# SMeter_RevA.net
KiCad netlist of a schematic drawn in EAGLE
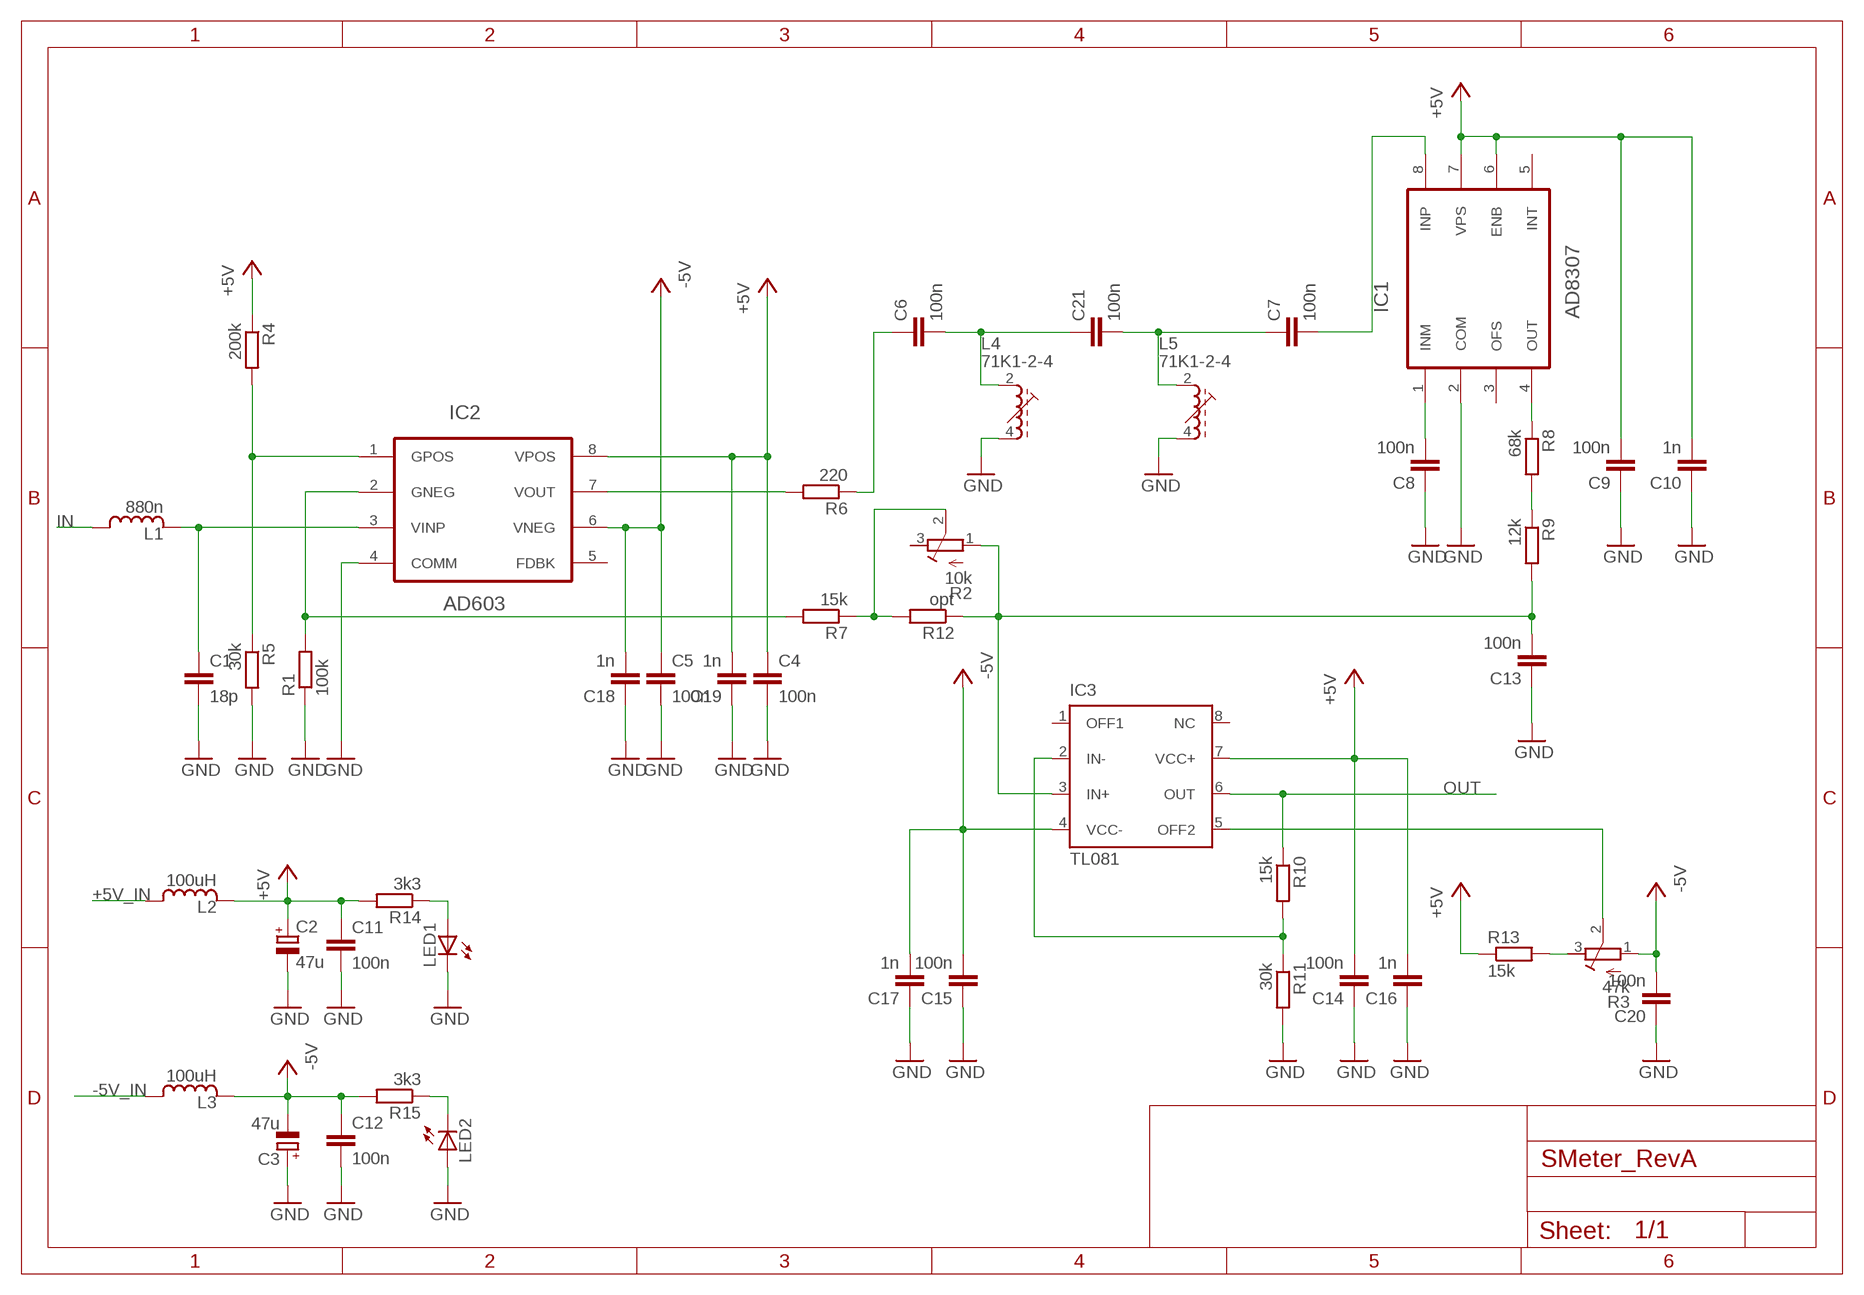
[diagram p0: schematic, sheet 1]

(export (version "E")
  (design (tool "Eeschema 10.0.6"))
  (components
    (comp (ref "C1")
      (value "18p")
      (footprint "eagle-import:C0805")
      (libsource (lib "eagle-import") (part "CC0805"))
    )
    (comp (ref "C2")
      (value "47u")
      (footprint "eagle-import:SMC_B")
      (libsource (lib "eagle-import") (part "C_POLARIZEDSMC_B"))
    )
    (comp (ref "C3")
      (value "47u")
      (footprint "eagle-import:SMC_B")
      (libsource (lib "eagle-import") (part "C_POLARIZEDSMC_B"))
    )
    (comp (ref "C4")
      (value "100n")
      (footprint "eagle-import:C0805")
      (libsource (lib "eagle-import") (part "CC0805"))
    )
    (comp (ref "C5")
      (value "100n")
      (footprint "eagle-import:C0805")
      (libsource (lib "eagle-import") (part "CC0805"))
    )
    (comp (ref "C6")
      (value "100n")
      (footprint "eagle-import:C0805")
      (libsource (lib "eagle-import") (part "CC0805"))
    )
    (comp (ref "C7")
      (value "100n")
      (footprint "eagle-import:C0805")
      (libsource (lib "eagle-import") (part "CC0805"))
    )
    (comp (ref "C8")
      (value "100n")
      (footprint "eagle-import:C0805")
      (libsource (lib "eagle-import") (part "CC0805"))
    )
    (comp (ref "C9")
      (value "100n")
      (footprint "eagle-import:C0805")
      (libsource (lib "eagle-import") (part "CC0805"))
    )
    (comp (ref "C10")
      (value "1n")
      (footprint "eagle-import:C0805")
      (libsource (lib "eagle-import") (part "CC0805"))
    )
    (comp (ref "C11")
      (value "100n")
      (footprint "eagle-import:C0805")
      (libsource (lib "eagle-import") (part "CC0805"))
    )
    (comp (ref "C12")
      (value "100n")
      (footprint "eagle-import:C0805")
      (libsource (lib "eagle-import") (part "CC0805"))
    )
    (comp (ref "C13")
      (value "100n")
      (footprint "eagle-import:C0805")
      (libsource (lib "eagle-import") (part "CC0805"))
    )
    (comp (ref "C14")
      (value "100n")
      (footprint "eagle-import:C0805")
      (libsource (lib "eagle-import") (part "CC0805"))
    )
    (comp (ref "C15")
      (value "100n")
      (footprint "eagle-import:C0805")
      (libsource (lib "eagle-import") (part "CC0805"))
    )
    (comp (ref "C16")
      (value "1n")
      (footprint "eagle-import:C0805")
      (libsource (lib "eagle-import") (part "CC0805"))
    )
    (comp (ref "C17")
      (value "1n")
      (footprint "eagle-import:C0805")
      (libsource (lib "eagle-import") (part "CC0805"))
    )
    (comp (ref "C18")
      (value "1n")
      (footprint "eagle-import:C0805")
      (libsource (lib "eagle-import") (part "CC0805"))
    )
    (comp (ref "C19")
      (value "1n")
      (footprint "eagle-import:C0805")
      (libsource (lib "eagle-import") (part "CC0805"))
    )
    (comp (ref "C20")
      (value "100n")
      (footprint "eagle-import:C0805")
      (libsource (lib "eagle-import") (part "CC0805"))
    )
    (comp (ref "C21")
      (value "100n")
      (footprint "eagle-import:C0805")
      (libsource (lib "eagle-import") (part "CC0805"))
    )
    (comp (ref "IC1")
      (value "AD8307")
      (footprint "eagle-import:SO8")
      (libsource (lib "eagle-import") (part "AD8307"))
    )
    (comp (ref "IC2")
      (value "AD603")
      (footprint "eagle-import:SO8")
      (libsource (lib "eagle-import") (part "AD603"))
    )
    (comp (ref "IC3")
      (value "TL081")
      (footprint "eagle-import:SOIC8")
      (libsource (lib "eagle-import") (part "TL081"))
    )
    (comp (ref "L1")
      (value "880n")
      (footprint "eagle-import:L0805")
      (libsource (lib "eagle-import") (part "INDUCTOR0805"))
    )
    (comp (ref "L2")
      (value "100uH")
      (footprint "eagle-import:LPS4018")
      (libsource (lib "eagle-import") (part "INDUCTORLPS4018"))
    )
    (comp (ref "L3")
      (value "100uH")
      (footprint "eagle-import:LPS4018")
      (libsource (lib "eagle-import") (part "INDUCTORLPS4018"))
    )
    (comp (ref "L4")
      (value "71K1-2-4")
      (footprint "eagle-import:71K")
      (libsource (lib "eagle-import") (part "71K1-2-4"))
    )
    (comp (ref "L5")
      (value "71K1-2-4")
      (footprint "eagle-import:71K")
      (libsource (lib "eagle-import") (part "71K1-2-4"))
    )
    (comp (ref "LED1")
      (value "LED0805")
      (footprint "eagle-import:LED0805")
      (libsource (lib "eagle-import") (part "LED0805"))
    )
    (comp (ref "LED2")
      (value "LED0805")
      (footprint "eagle-import:LED0805")
      (libsource (lib "eagle-import") (part "LED0805"))
    )
    (comp (ref "R1")
      (value "100k")
      (footprint "eagle-import:R0805")
      (libsource (lib "eagle-import") (part "RESISTORR0805"))
    )
    (comp (ref "R2")
      (value "10k")
      (footprint "eagle-import:RTRIM3224X")
      (libsource (lib "eagle-import") (part "TRIMMER3224X"))
    )
    (comp (ref "R3")
      (value "47k")
      (footprint "eagle-import:RTRIM3224X")
      (libsource (lib "eagle-import") (part "TRIMMER3224X"))
    )
    (comp (ref "R4")
      (value "200k")
      (footprint "eagle-import:R0805")
      (libsource (lib "eagle-import") (part "RESISTORR0805"))
    )
    (comp (ref "R5")
      (value "30k")
      (footprint "eagle-import:R0805")
      (libsource (lib "eagle-import") (part "RESISTORR0805"))
    )
    (comp (ref "R6")
      (value "220")
      (footprint "eagle-import:R0805")
      (libsource (lib "eagle-import") (part "RESISTORR0805"))
    )
    (comp (ref "R7")
      (value "15k")
      (footprint "eagle-import:R0805")
      (libsource (lib "eagle-import") (part "RESISTORR0805"))
    )
    (comp (ref "R8")
      (value "68k")
      (footprint "eagle-import:R0805")
      (libsource (lib "eagle-import") (part "RESISTORR0805"))
    )
    (comp (ref "R9")
      (value "12k")
      (footprint "eagle-import:R0805")
      (libsource (lib "eagle-import") (part "RESISTORR0805"))
    )
    (comp (ref "R10")
      (value "15k")
      (footprint "eagle-import:R0805")
      (libsource (lib "eagle-import") (part "RESISTORR0805"))
    )
    (comp (ref "R11")
      (value "30k")
      (footprint "eagle-import:R0805")
      (libsource (lib "eagle-import") (part "RESISTORR0805"))
    )
    (comp (ref "R12")
      (value "opt")
      (footprint "eagle-import:R0805")
      (libsource (lib "eagle-import") (part "RESISTORR0805"))
    )
    (comp (ref "R13")
      (value "15k")
      (footprint "eagle-import:R0805")
      (libsource (lib "eagle-import") (part "RESISTORR0805"))
    )
    (comp (ref "R14")
      (value "3k3")
      (footprint "eagle-import:R0805")
      (libsource (lib "eagle-import") (part "RESISTORR0805"))
    )
    (comp (ref "R15")
      (value "3k3")
      (footprint "eagle-import:R0805")
      (libsource (lib "eagle-import") (part "RESISTORR0805"))
    )
  )
  (nets
    (net (code "1") (name "+5V") (class "Default")
      (node (ref "C10") (pin "2") (pinfunction "2_2") (pintype "passive"))
      (node (ref "C11") (pin "1") (pinfunction "1_1") (pintype "passive"))
      (node (ref "C14") (pin "2") (pinfunction "2_2") (pintype "passive"))
      (node (ref "C16") (pin "2") (pinfunction "2_2") (pintype "passive"))
      (node (ref "C19") (pin "2") (pinfunction "2_2") (pintype "passive"))
      (node (ref "C2") (pin "+") (pinfunction "+_+") (pintype "passive"))
      (node (ref "C4") (pin "1") (pinfunction "1_1") (pintype "passive"))
      (node (ref "C9") (pin "2") (pinfunction "2_2") (pintype "passive"))
      (node (ref "IC1") (pin "6") (pinfunction "ENB_6") (pintype "passive"))
      (node (ref "IC1") (pin "7") (pinfunction "VPS_7") (pintype "passive"))
      (node (ref "IC2") (pin "8") (pinfunction "VPOS_8") (pintype "power_in"))
      (node (ref "IC3") (pin "7") (pinfunction "VCC+_7") (pintype "input"))
      (node (ref "L2") (pin "2") (pinfunction "2_2") (pintype "passive"))
      (node (ref "R13") (pin "1") (pinfunction "1_1") (pintype "passive"))
      (node (ref "R14") (pin "2") (pinfunction "2_2") (pintype "passive"))
      (node (ref "R4") (pin "1") (pinfunction "1_1") (pintype "passive"))
    )
    (net (code "2") (name "-5V") (class "Default")
      (node (ref "C12") (pin "1") (pinfunction "1_1") (pintype "passive"))
      (node (ref "C15") (pin "2") (pinfunction "2_2") (pintype "passive"))
      (node (ref "C17") (pin "2") (pinfunction "2_2") (pintype "passive"))
      (node (ref "C18") (pin "2") (pinfunction "2_2") (pintype "passive"))
      (node (ref "C20") (pin "2") (pinfunction "2_2") (pintype "passive"))
      (node (ref "C3") (pin "-") (pinfunction "-_-") (pintype "passive"))
      (node (ref "C5") (pin "1") (pinfunction "1_1") (pintype "passive"))
      (node (ref "IC2") (pin "6") (pinfunction "VNEG_6") (pintype "passive"))
      (node (ref "IC3") (pin "4") (pinfunction "VCC-_4") (pintype "power_in"))
      (node (ref "L3") (pin "2") (pinfunction "2_2") (pintype "passive"))
      (node (ref "R15") (pin "2") (pinfunction "2_2") (pintype "passive"))
      (node (ref "R3") (pin "1") (pinfunction "CCW_1") (pintype "passive"))
    )
    (net (code "3") (name "/+5V_IN") (class "Default")
      (node (ref "L2") (pin "1") (pinfunction "1_1") (pintype "passive"))
    )
    (net (code "4") (name "/-5V_IN") (class "Default")
      (node (ref "L3") (pin "1") (pinfunction "1_1") (pintype "passive"))
    )
    (net (code "5") (name "/IN") (class "Default")
      (node (ref "L1") (pin "1") (pinfunction "1_1") (pintype "passive"))
    )
    (net (code "6") (name "/OUT") (class "Default")
      (node (ref "IC3") (pin "6") (pinfunction "OUT_6") (pintype "passive"))
      (node (ref "R10") (pin "1") (pinfunction "1_1") (pintype "passive"))
    )
    (net (code "7") (name "GND") (class "Default")
      (node (ref "C1") (pin "2") (pinfunction "2_2") (pintype "passive"))
      (node (ref "C10") (pin "1") (pinfunction "1_1") (pintype "passive"))
      (node (ref "C11") (pin "2") (pinfunction "2_2") (pintype "passive"))
      (node (ref "C12") (pin "2") (pinfunction "2_2") (pintype "passive"))
      (node (ref "C13") (pin "1") (pinfunction "1_1") (pintype "passive"))
      (node (ref "C14") (pin "1") (pinfunction "1_1") (pintype "passive"))
      (node (ref "C15") (pin "1") (pinfunction "1_1") (pintype "passive"))
      (node (ref "C16") (pin "1") (pinfunction "1_1") (pintype "passive"))
      (node (ref "C17") (pin "1") (pinfunction "1_1") (pintype "passive"))
      (node (ref "C18") (pin "1") (pinfunction "1_1") (pintype "passive"))
      (node (ref "C19") (pin "1") (pinfunction "1_1") (pintype "passive"))
      (node (ref "C2") (pin "-") (pinfunction "-_-") (pintype "passive"))
      (node (ref "C20") (pin "1") (pinfunction "1_1") (pintype "passive"))
      (node (ref "C3") (pin "+") (pinfunction "+_+") (pintype "passive"))
      (node (ref "C4") (pin "2") (pinfunction "2_2") (pintype "passive"))
      (node (ref "C5") (pin "2") (pinfunction "2_2") (pintype "passive"))
      (node (ref "C8") (pin "1") (pinfunction "1_1") (pintype "passive"))
      (node (ref "C9") (pin "1") (pinfunction "1_1") (pintype "passive"))
      (node (ref "IC1") (pin "2") (pinfunction "COM_2") (pintype "input"))
      (node (ref "IC2") (pin "4") (pinfunction "COMM_4") (pintype "power_in"))
      (node (ref "L4") (pin "4") (pinfunction "E_4") (pintype "passive"))
      (node (ref "L5") (pin "4") (pinfunction "E_4") (pintype "passive"))
      (node (ref "LED1") (pin "C") (pinfunction "C_C") (pintype "passive"))
      (node (ref "LED2") (pin "A") (pinfunction "A_A") (pintype "passive"))
      (node (ref "R1") (pin "1") (pinfunction "1_1") (pintype "passive"))
      (node (ref "R11") (pin "2") (pinfunction "2_2") (pintype "passive"))
      (node (ref "R5") (pin "2") (pinfunction "2_2") (pintype "passive"))
    )
    (net (code "8") (name "Net-(C6-Pad1)") (class "Default")
      (node (ref "C6") (pin "1") (pinfunction "1_1") (pintype "passive"))
      (node (ref "R6") (pin "1") (pinfunction "1_1") (pintype "passive"))
    )
    (net (code "9") (name "Net-(IC1-INM)") (class "Default")
      (node (ref "C8") (pin "2") (pinfunction "2_2") (pintype "passive"))
      (node (ref "IC1") (pin "1") (pinfunction "INM_1") (pintype "input"))
    )
    (net (code "10") (name "Net-(IC1-INP)") (class "Default")
      (node (ref "C7") (pin "2") (pinfunction "2_2") (pintype "passive"))
      (node (ref "IC1") (pin "8") (pinfunction "INP_8") (pintype "power_in"))
    )
    (net (code "11") (name "Net-(IC1-OUT)") (class "Default")
      (node (ref "IC1") (pin "4") (pinfunction "OUT_4") (pintype "power_in"))
      (node (ref "R8") (pin "1") (pinfunction "1_1") (pintype "passive"))
    )
    (net (code "12") (name "Net-(IC2-GNEG)") (class "Default")
      (node (ref "IC2") (pin "2") (pinfunction "GNEG_2") (pintype "input"))
      (node (ref "R1") (pin "2") (pinfunction "2_2") (pintype "passive"))
      (node (ref "R7") (pin "2") (pinfunction "2_2") (pintype "passive"))
    )
    (net (code "13") (name "Net-(IC2-GPOS)") (class "Default")
      (node (ref "IC2") (pin "1") (pinfunction "GPOS_1") (pintype "input"))
      (node (ref "R4") (pin "2") (pinfunction "2_2") (pintype "passive"))
      (node (ref "R5") (pin "1") (pinfunction "1_1") (pintype "passive"))
    )
    (net (code "14") (name "Net-(IC2-VINP)") (class "Default")
      (node (ref "C1") (pin "1") (pinfunction "1_1") (pintype "passive"))
      (node (ref "IC2") (pin "3") (pinfunction "VINP_3") (pintype "bidirectional"))
      (node (ref "L1") (pin "2") (pinfunction "2_2") (pintype "passive"))
    )
    (net (code "15") (name "Net-(IC2-VOUT)") (class "Default")
      (node (ref "IC2") (pin "7") (pinfunction "VOUT_7") (pintype "passive"))
      (node (ref "R6") (pin "2") (pinfunction "2_2") (pintype "passive"))
    )
    (net (code "16") (name "Net-(IC3-IN+)") (class "Default")
      (node (ref "C13") (pin "2") (pinfunction "2_2") (pintype "passive"))
      (node (ref "IC3") (pin "3") (pinfunction "IN+_3") (pintype "input"))
      (node (ref "R12") (pin "1") (pinfunction "1_1") (pintype "passive"))
      (node (ref "R2") (pin "1") (pinfunction "CCW_1") (pintype "passive"))
      (node (ref "R9") (pin "2") (pinfunction "2_2") (pintype "passive"))
    )
    (net (code "17") (name "Net-(IC3-IN-)") (class "Default")
      (node (ref "IC3") (pin "2") (pinfunction "IN-_2") (pintype "input"))
      (node (ref "R10") (pin "2") (pinfunction "2_2") (pintype "passive"))
      (node (ref "R11") (pin "1") (pinfunction "1_1") (pintype "passive"))
    )
    (net (code "18") (name "Net-(IC3-OFF2)") (class "Default")
      (node (ref "IC3") (pin "5") (pinfunction "OFF2_5") (pintype "passive"))
      (node (ref "R3") (pin "2") (pinfunction "WIPER_2") (pintype "passive"))
    )
    (net (code "19") (name "Net-(L4A-A)") (class "Default")
      (node (ref "C21") (pin "1") (pinfunction "1_1") (pintype "passive"))
      (node (ref "C6") (pin "2") (pinfunction "2_2") (pintype "passive"))
      (node (ref "L4") (pin "2") (pinfunction "A_2") (pintype "passive"))
    )
    (net (code "20") (name "Net-(L5A-A)") (class "Default")
      (node (ref "C21") (pin "2") (pinfunction "2_2") (pintype "passive"))
      (node (ref "C7") (pin "1") (pinfunction "1_1") (pintype "passive"))
      (node (ref "L5") (pin "2") (pinfunction "A_2") (pintype "passive"))
    )
    (net (code "21") (name "Net-(LED1-PadA)") (class "Default")
      (node (ref "LED1") (pin "A") (pinfunction "A_A") (pintype "passive"))
      (node (ref "R14") (pin "1") (pinfunction "1_1") (pintype "passive"))
    )
    (net (code "22") (name "Net-(LED2-PadC)") (class "Default")
      (node (ref "LED2") (pin "C") (pinfunction "C_C") (pintype "passive"))
      (node (ref "R15") (pin "1") (pinfunction "1_1") (pintype "passive"))
    )
    (net (code "23") (name "Net-(R2-WIPER)") (class "Default")
      (node (ref "R12") (pin "2") (pinfunction "2_2") (pintype "passive"))
      (node (ref "R2") (pin "2") (pinfunction "WIPER_2") (pintype "passive"))
      (node (ref "R7") (pin "1") (pinfunction "1_1") (pintype "passive"))
    )
    (net (code "24") (name "Net-(R3-CW)") (class "Default")
      (node (ref "R13") (pin "2") (pinfunction "2_2") (pintype "passive"))
      (node (ref "R3") (pin "3") (pinfunction "CW_3") (pintype "passive"))
    )
    (net (code "25") (name "Net-(R8-Pad2)") (class "Default")
      (node (ref "R8") (pin "2") (pinfunction "2_2") (pintype "passive"))
      (node (ref "R9") (pin "1") (pinfunction "1_1") (pintype "passive"))
    )
    (net (code "26") (name "unconnected-(IC1-INT-Pad5)") (class "Default")
      (node (ref "IC1") (pin "5") (pinfunction "INT_5") (pintype "passive"))
    )
    (net (code "27") (name "unconnected-(IC1-OFS-Pad3)") (class "Default")
      (node (ref "IC1") (pin "3") (pinfunction "OFS_3") (pintype "bidirectional"))
    )
    (net (code "28") (name "unconnected-(IC2-FDBK-Pad5)") (class "Default")
      (node (ref "IC2") (pin "5") (pinfunction "FDBK_5") (pintype "passive"))
    )
    (net (code "29") (name "unconnected-(IC3-NC-Pad8)") (class "Default")
      (node (ref "IC3") (pin "8") (pinfunction "NC_8") (pintype "input"))
    )
    (net (code "30") (name "unconnected-(IC3-OFF1-Pad1)") (class "Default")
      (node (ref "IC3") (pin "1") (pinfunction "OFF1_1") (pintype "input"))
    )
    (net (code "31") (name "unconnected-(R2-CW-Pad3)") (class "Default")
      (node (ref "R2") (pin "3") (pinfunction "CW_3") (pintype "passive"))
    )
  )
)
